# RF_Antenna_Power.net
KiCad netlist of a schematic drawn in Altium Designer
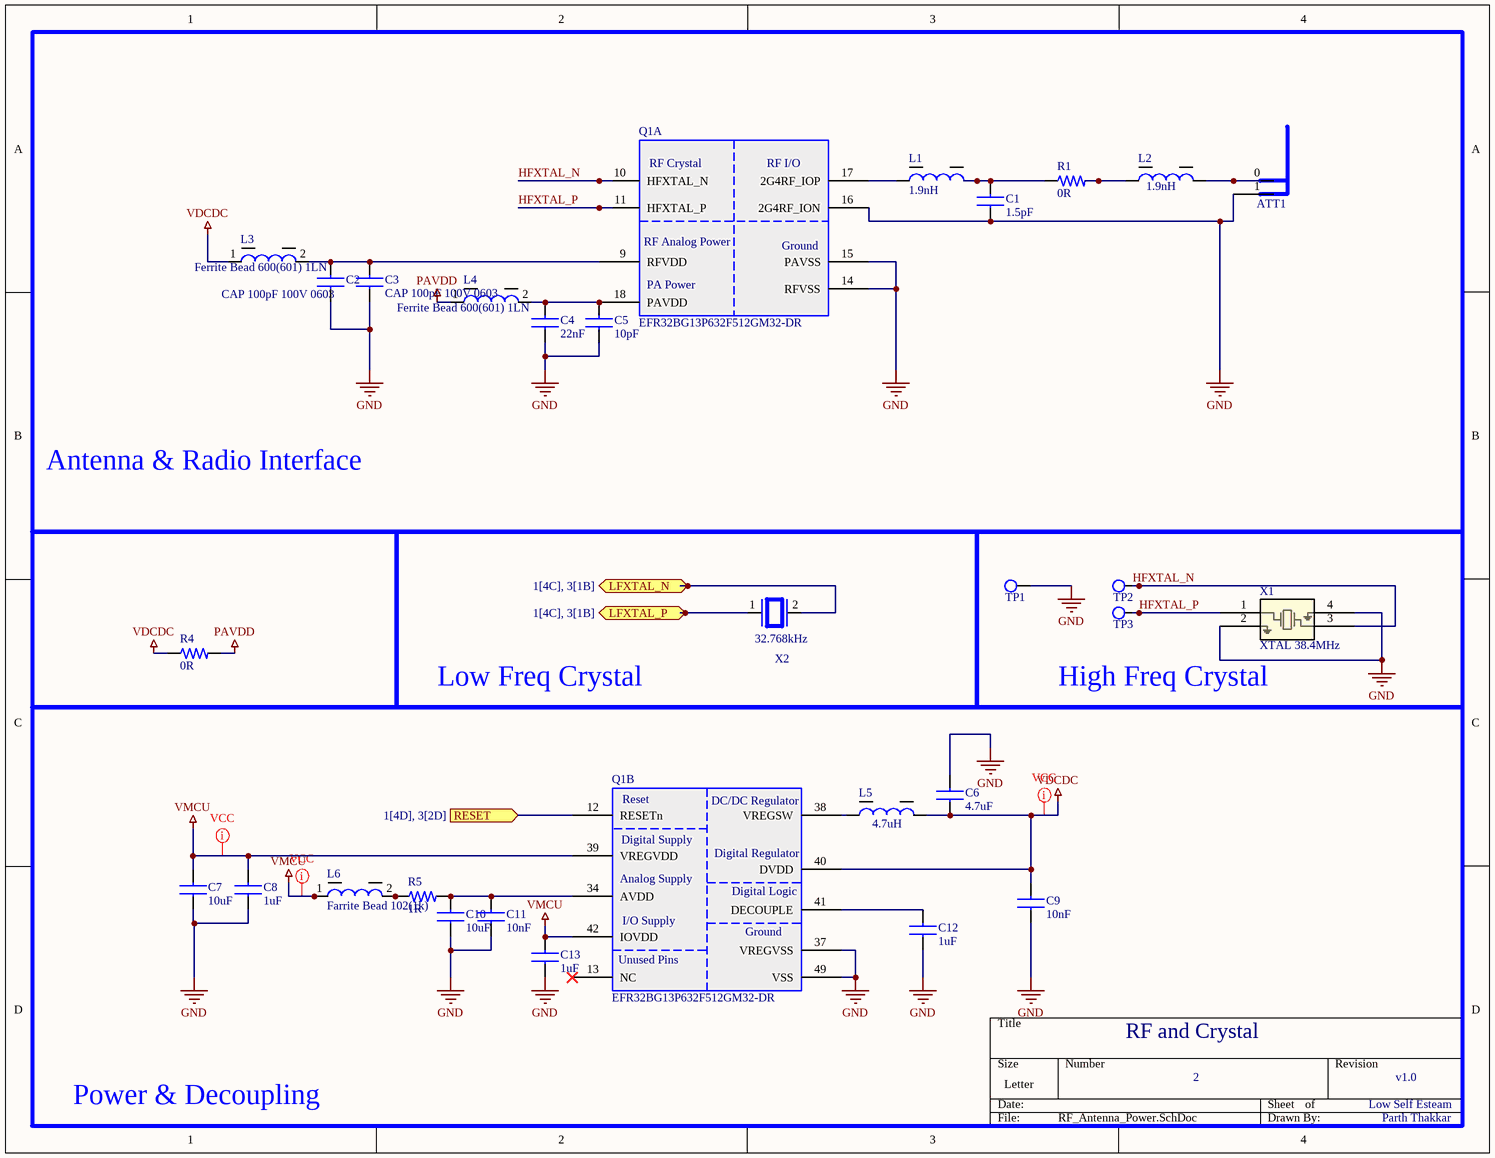
[diagram p0: RF_Antenna_Power.SchDoc]

(export (version "E")
  (design (tool "Eeschema 10.0.6"))
  (components
    (comp (ref "ATT1")
      (value "F_Interverted")
      (footprint "F_Inverted")
      (description "For 50Ohm impedence, Inverted F antenna")
      (libsource (lib "Keyboard_parts") (part "F_Interverted"))
    )
    (comp (ref "C1")
      (value "1.5pF")
      (footprint "Capacitor 0402")
      (fields
        (field (name "MANUFACTURER") "Murata")
        (field (name "MANUFACTURER PART NUMBER") "GJM1555C1H1R5WB01D")
        (field (name "Comment") "CAP 1.5pF 50V 0402")
      )
      (libsource (lib "Keyboard_parts") (part "CAP 1.5pF 50V 0402"))
    )
    (comp (ref "C2")
      (value "CAP 100pF 100V 0603")
      (footprint "Capacitor 0603")
      (fields
        (field (name "MANUFACTURER") "Murata")
        (field (name "MANUFACTURER PART NUMBER") "GCM1885C2A101JA16D")
      )
      (libsource (lib "Keyboard_parts") (part "CAP 100pF 100V 0603"))
    )
    (comp (ref "C3")
      (value "CAP 100pF 100V 0603")
      (footprint "Capacitor 0603")
      (fields
        (field (name "MANUFACTURER") "Murata")
        (field (name "MANUFACTURER PART NUMBER") "GCM1885C2A101JA16D")
      )
      (libsource (lib "Keyboard_parts") (part "CAP 100pF 100V 0603"))
    )
    (comp (ref "C4")
      (value "22nF")
      (footprint "Capacitor 0603")
      (fields
        (field (name "MANUFACTURER") "Murata")
        (field (name "MANUFACTURER PART NUMBER") "GRM155R71H223KA12D")
        (field (name "Comment") "CAP 220nF 50V 0603")
      )
      (libsource (lib "Keyboard_parts") (part "CAP 220nF 50V 0603"))
    )
    (comp (ref "C5")
      (value "10pF")
      (footprint "Capacitor 0603")
      (fields
        (field (name "MANUFACTURER") "Murata")
        (field (name "MANUFACTURER PART NUMBER") "GRM1555C1H100FA01D")
        (field (name "Comment") "CAP 10pF 50V 0603")
      )
      (libsource (lib "Keyboard_parts") (part "CAP 10pF 50V 0603"))
    )
    (comp (ref "C6")
      (value "4.7uF")
      (footprint "Capacitor 0603")
      (fields
        (field (name "MANUFACTURER") "Murata")
        (field (name "MANUFACTURER PART NUMBER") "GRT188R61E475KE13D")
        (field (name "Comment") "CAP 4.7uF 25V 0603")
      )
      (libsource (lib "Keyboard_parts") (part "CAP 4.7uF 25V 0603"))
    )
    (comp (ref "C7")
      (value "10uF")
      (footprint "Capacitor 0603")
      (fields
        (field (name "MANUFACTURER") "Murata")
        (field (name "MANUFACTURER PART NUMBER") "GRM188R61A106ME69D")
        (field (name "Comment") "CAP 10uF 10V 0603")
      )
      (libsource (lib "Keyboard_parts") (part "CAP 10uF 10V 0603"))
    )
    (comp (ref "C8")
      (value "1uF")
      (footprint "Capacitor 0603")
      (fields
        (field (name "MANUFACTURER") "Murata")
        (field (name "MANUFACTURER PART NUMBER") "GRM188R61A105KA61D")
        (field (name "Comment") "CAP 1uF 10V 0603")
      )
      (libsource (lib "Keyboard_parts") (part "CAP 1uF 10V 0603"))
    )
    (comp (ref "C9")
      (value "10nF")
      (footprint "Capacitor 0603")
      (fields
        (field (name "MANUFACTURER") "Murata")
        (field (name "MANUFACTURER PART NUMBER") "GCM188R72A103KA37D")
        (field (name "Comment") "CAP 0.1uF 100V 0603")
      )
      (libsource (lib "Keyboard_parts") (part "CAP 0.1uF 100V 0603"))
    )
    (comp (ref "C10")
      (value "10uF")
      (footprint "Capacitor 0603")
      (fields
        (field (name "MANUFACTURER") "Murata")
        (field (name "MANUFACTURER PART NUMBER") "GRM188R61A106ME69D")
        (field (name "Comment") "CAP 10uF 10V 0603")
      )
      (libsource (lib "Keyboard_parts") (part "CAP 10uF 10V 0603"))
    )
    (comp (ref "C11")
      (value "10nF")
      (footprint "Capacitor 0603")
      (fields
        (field (name "MANUFACTURER") "Murata")
        (field (name "MANUFACTURER PART NUMBER") "GCM188R72A103KA37D")
        (field (name "Comment") "CAP 10nF 100V 0603")
      )
      (libsource (lib "Keyboard_parts") (part "CAP 10nF 100V 0603"))
    )
    (comp (ref "C12")
      (value "1uF")
      (footprint "Capacitor 0603")
      (fields
        (field (name "MANUFACTURER") "Murata")
        (field (name "MANUFACTURER PART NUMBER") "GRM188R61A105KA61D")
        (field (name "Comment") "CAP 1uF 10V 0603")
      )
      (libsource (lib "Keyboard_parts") (part "CAP 1uF 10V 0603"))
    )
    (comp (ref "C13")
      (value "1uF")
      (footprint "Capacitor 0603")
      (fields
        (field (name "MANUFACTURER") "Murata")
        (field (name "MANUFACTURER PART NUMBER") "GRM188R61A105KA61D")
        (field (name "Comment") "CAP 1uF 10V 0603")
      )
      (libsource (lib "Keyboard_parts") (part "CAP 1uF 10V 0603"))
    )
    (comp (ref "L1")
      (value "1.9nH")
      (footprint "Ferrite 0402")
      (description "Inductor Chip 1.9nH 0.3nH Tolerance 2-Pin 0402 Paper T/R")
      (fields
        (field (name "MANUFACTURER") "Murata")
        (field (name "MANUFACTURER PART NUMBER") "LQG15WZ1N9S02D")
      )
      (libsource (lib "Keyboard_parts") (part "IND 1.9nH 0402"))
    )
    (comp (ref "L2")
      (value "1.9nH")
      (footprint "Ferrite 0402")
      (description "Inductor Chip 1.9nH 0.3nH Tolerance 2-Pin 0402 Paper T/R")
      (fields
        (field (name "MANUFACTURER") "Murata")
        (field (name "MANUFACTURER PART NUMBER") "LQG15WZ1N9S02D")
      )
      (libsource (lib "Keyboard_parts") (part "IND 1.9nH 0402"))
    )
    (comp (ref "L3")
      (value "Ferrite Bead 600(601) 1LN")
      (footprint "Ferrite 0603")
      (description "RFVDD, PAVDD, EFR")
      (fields
        (field (name "MANUFACTURER") "Murata")
        (field (name "MANUFACTURER PART NUMBER") "BLM18AG601SN1D")
      )
      (libsource (lib "Keyboard_parts") (part "Ferrite Bead 600(601) 1LN"))
    )
    (comp (ref "L4")
      (value "Ferrite Bead 600(601) 1LN")
      (footprint "Ferrite 0603")
      (description "RFVDD, PAVDD, EFR")
      (fields
        (field (name "MANUFACTURER") "Murata")
        (field (name "MANUFACTURER PART NUMBER") "BLM18AG601SN1D")
      )
      (libsource (lib "Keyboard_parts") (part "Ferrite Bead 600(601) 1LN"))
    )
    (comp (ref "L5")
      (value "IND 4.7uH 1515")
      (footprint "IND 22uH (1.6x4.3)")
      (description "General Purpose Inductor, 4.7uH, 30%, 1 Element, Ferrite-Core, SMD, 1515")
      (fields
        (field (name "MANUFACTURER") "Wurth Electronics")
        (field (name "MANUFACTURER PART NUMBER") "744031004")
        (field (name "INDUCTANCE-NOM (L)") "4.7uH")
      )
      (libsource (lib "Keyboard_parts") (part "IND 4.7uH 1515"))
    )
    (comp (ref "L6")
      (value "Farrite Bead 102(1k)")
      (footprint "Ferrite 0402")
      (description "Ferrite Chip, 1 Function(s), 0.05A, 2 Pin(s)")
      (fields
        (field (name "MANUFACTURER") "Wurth Electronics")
        (field (name "MANUFACTURER PART NUMBER") "742841210")
      )
      (libsource (lib "Keyboard_parts") (part "Farrite Bead 102(1k)"))
    )
    (comp (ref "Q1")
      (value "EFR32BG13P632F512GM32-DR")
      (footprint "EFR32BG")
      (description "BLue Gecko")
      (fields (field (name "MANUFACTURER") "Silicon Labs"))
      (libsource (lib "Keyboard_parts") (part "EFR32BG13P632F512GM32-DR"))
    )
    (comp (ref "R1")
      (value "0R")
      (footprint "Resistor 0402")
      (description "Metal Glaze/thick Film, 0.0625W, 0ohm, Surface Mount, 0402")
      (fields
        (field (name "MANUFACTURER") "Yageo")
        (field (name "MANUFACTURER PART NUMBER") "RC0402JR-070RL")
      )
      (libsource (lib "Keyboard_parts") (part "RES 0R 0402"))
    )
    (comp (ref "R4")
      (value "0R")
      (footprint "Resistor 0402")
      (description "Metal Glaze/thick Film, 0.0625W, 0ohm, Surface Mount, 0402")
      (fields
        (field (name "MANUFACTURER") "Yageo")
        (field (name "MANUFACTURER PART NUMBER") "RC0402JR-070RL")
      )
      (libsource (lib "Keyboard_parts") (part "RES 0R 0402"))
    )
    (comp (ref "R5")
      (value "1R")
      (footprint "Resistor 0603")
      (fields
        (field (name "MANUFACTURER") "Yageo")
        (field (name "MANUFACTURER PART NUMBER") "RC0603FR-071RL")
        (field (name "TOLERANCE") "1%")
      )
      (libsource (lib "Keyboard_parts") (part "RES 1R 0603"))
    )
    (comp (ref "TP1")
      (value "Test point")
      (footprint "Test Point")
      (libsource (lib "Keyboard_parts") (part "Test point"))
    )
    (comp (ref "TP2")
      (value "Test point")
      (footprint "Test Point")
      (libsource (lib "Keyboard_parts") (part "Test point"))
    )
    (comp (ref "TP3")
      (value "Test point")
      (footprint "Test Point")
      (libsource (lib "Keyboard_parts") (part "Test point"))
    )
    (comp (ref "X1")
      (value "XTAL 38.4MHz")
      (footprint "XTAL 38.4MHz")
      (description "Crystal 38.4000MHZ 10PF SMD")
      (fields
        (field (name "MANUFACTURER") "Murata")
        (field (name "MANUFACTURER PART NUMBER") "XRCGB38M400F1S3JR0")
      )
      (libsource (lib "Keyboard_parts") (part "XTAL 38.4MHz"))
    )
    (comp (ref "X2")
      (value "32.768kHz")
      (footprint "XTAL_32.768KHZ-T")
      (description "Parallel - Fundamental Quartz Crystal, 0.032768MHz Nom")
      (fields
        (field (name "MANUFACTURER") "Abracon")
        (field (name "MANUFACTURER PART NUMBER") "ABS07-32.768KHZ-T")
      )
      (libsource (lib "Keyboard_parts") (part "XTAL 32.768kHz"))
    )
  )
  (nets
    (net (code "1") (name "/HFXTAL_N") (class "Default")
      (node (ref "Q1") (pin "10") (pinfunction "HFXTAL_N_10") (pintype "passive"))
      (node (ref "TP2") (pin "1") (pinfunction "1_1") (pintype "passive"))
      (node (ref "X1") (pin "3") (pinfunction "3_3") (pintype "passive"))
    )
    (net (code "2") (name "/HFXTAL_P") (class "Default")
      (node (ref "Q1") (pin "11") (pinfunction "HFXTAL_P_11") (pintype "passive"))
      (node (ref "TP3") (pin "1") (pinfunction "1_1") (pintype "passive"))
      (node (ref "X1") (pin "1") (pinfunction "1_1") (pintype "passive"))
    )
    (net (code "3") (name "/LFXTAL_N") (class "Default")
      (node (ref "X2") (pin "2") (pinfunction "2_2") (pintype "passive"))
    )
    (net (code "4") (name "/LFXTAL_P") (class "Default")
      (node (ref "X2") (pin "1") (pinfunction "1_1") (pintype "passive"))
    )
    (net (code "5") (name "/RESET") (class "Default")
      (node (ref "Q1") (pin "12") (pinfunction "RESETn_12") (pintype "passive"))
    )
    (net (code "6") (name "GND") (class "Default")
      (node (ref "ATT1") (pin "1") (pinfunction "GND_1") (pintype "passive"))
      (node (ref "C1") (pin "2") (pinfunction "2_2") (pintype "passive"))
      (node (ref "C10") (pin "2") (pinfunction "2_2") (pintype "passive"))
      (node (ref "C11") (pin "2") (pinfunction "2_2") (pintype "passive"))
      (node (ref "C12") (pin "2") (pinfunction "2_2") (pintype "passive"))
      (node (ref "C13") (pin "2") (pinfunction "2_2") (pintype "passive"))
      (node (ref "C2") (pin "2") (pinfunction "2_2") (pintype "passive"))
      (node (ref "C3") (pin "2") (pinfunction "2_2") (pintype "passive"))
      (node (ref "C4") (pin "2") (pinfunction "2_2") (pintype "passive"))
      (node (ref "C5") (pin "2") (pinfunction "2_2") (pintype "passive"))
      (node (ref "C6") (pin "2") (pinfunction "2_2") (pintype "passive"))
      (node (ref "C7") (pin "2") (pinfunction "2_2") (pintype "passive"))
      (node (ref "C8") (pin "2") (pinfunction "2_2") (pintype "passive"))
      (node (ref "C9") (pin "2") (pinfunction "2_2") (pintype "passive"))
      (node (ref "Q1") (pin "14") (pinfunction "RFVSS_14") (pintype "power_in"))
      (node (ref "Q1") (pin "15") (pinfunction "PAVSS_15") (pintype "power_in"))
      (node (ref "Q1") (pin "16") (pinfunction "2G4RF_ION_16") (pintype "passive"))
      (node (ref "Q1") (pin "37") (pinfunction "VREGVSS_37") (pintype "power_in"))
      (node (ref "Q1") (pin "49") (pinfunction "VSS_49") (pintype "power_in"))
      (node (ref "TP1") (pin "1") (pinfunction "1_1") (pintype "passive"))
      (node (ref "X1") (pin "2") (pinfunction "2_2") (pintype "passive"))
      (node (ref "X1") (pin "4") (pinfunction "4_4") (pintype "passive"))
    )
    (net (code "7") (name "Net-(ATT1-FEED)") (class "Default")
      (node (ref "ATT1") (pin "0") (pinfunction "FEED_0") (pintype "passive"))
      (node (ref "L2") (pin "2") (pinfunction "2_2") (pintype "passive"))
    )
    (net (code "8") (name "Net-(C1-Pad1)") (class "Default")
      (node (ref "C1") (pin "1") (pinfunction "1_1") (pintype "passive"))
      (node (ref "L1") (pin "2") (pinfunction "2_2") (pintype "passive"))
      (node (ref "R1") (pin "1") (pinfunction "1_1") (pintype "passive"))
    )
    (net (code "9") (name "Net-(L2-Pad1)") (class "Default")
      (node (ref "L2") (pin "1") (pinfunction "1_1") (pintype "passive"))
      (node (ref "R1") (pin "2") (pinfunction "2_2") (pintype "passive"))
    )
    (net (code "10") (name "Net-(L6-Pad2)") (class "Default")
      (node (ref "L6") (pin "2") (pinfunction "2_2") (pintype "passive"))
      (node (ref "R5") (pin "1") (pinfunction "1_1") (pintype "passive"))
    )
    (net (code "11") (name "Net-(Q1A-2G4RF_IOP)") (class "Default")
      (node (ref "L1") (pin "1") (pinfunction "1_1") (pintype "passive"))
      (node (ref "Q1") (pin "17") (pinfunction "2G4RF_IOP_17") (pintype "passive"))
    )
    (net (code "12") (name "Net-(Q1A-PAVDD)") (class "Default")
      (node (ref "C4") (pin "1") (pinfunction "1_1") (pintype "passive"))
      (node (ref "C5") (pin "1") (pinfunction "1_1") (pintype "passive"))
      (node (ref "L4") (pin "2") (pinfunction "2_2") (pintype "passive"))
      (node (ref "Q1") (pin "18") (pinfunction "PAVDD_18") (pintype "power_in"))
    )
    (net (code "13") (name "Net-(Q1A-RFVDD)") (class "Default")
      (node (ref "C2") (pin "1") (pinfunction "1_1") (pintype "passive"))
      (node (ref "C3") (pin "1") (pinfunction "1_1") (pintype "passive"))
      (node (ref "L3") (pin "2") (pinfunction "2_2") (pintype "passive"))
      (node (ref "Q1") (pin "9") (pinfunction "RFVDD_9") (pintype "power_in"))
    )
    (net (code "14") (name "Net-(Q1B-AVDD)") (class "Default")
      (node (ref "C10") (pin "1") (pinfunction "1_1") (pintype "passive"))
      (node (ref "C11") (pin "1") (pinfunction "1_1") (pintype "passive"))
      (node (ref "Q1") (pin "34") (pinfunction "AVDD_34") (pintype "power_in"))
      (node (ref "R5") (pin "2") (pinfunction "2_2") (pintype "passive"))
    )
    (net (code "15") (name "Net-(Q1B-DECOUPLE)") (class "Default")
      (node (ref "C12") (pin "1") (pinfunction "1_1") (pintype "passive"))
      (node (ref "Q1") (pin "41") (pinfunction "DECOUPLE_41") (pintype "passive"))
    )
    (net (code "16") (name "Net-(Q1B-VREGSW)") (class "Default")
      (node (ref "L5") (pin "1") (pinfunction "1_1") (pintype "passive"))
      (node (ref "Q1") (pin "38") (pinfunction "VREGSW_38") (pintype "power_in"))
    )
    (net (code "17") (name "PAVDD") (class "Default")
      (node (ref "L4") (pin "1") (pinfunction "1_1") (pintype "passive"))
      (node (ref "R4") (pin "2") (pinfunction "2_2") (pintype "passive"))
    )
    (net (code "18") (name "VDCDC") (class "Default")
      (node (ref "C6") (pin "1") (pinfunction "1_1") (pintype "passive"))
      (node (ref "C9") (pin "1") (pinfunction "1_1") (pintype "passive"))
      (node (ref "L3") (pin "1") (pinfunction "1_1") (pintype "passive"))
      (node (ref "L5") (pin "2") (pinfunction "2_2") (pintype "passive"))
      (node (ref "Q1") (pin "40") (pinfunction "DVDD_40") (pintype "power_in"))
      (node (ref "R4") (pin "1") (pinfunction "1_1") (pintype "passive"))
    )
    (net (code "19") (name "VMCU") (class "Default")
      (node (ref "C13") (pin "1") (pinfunction "1_1") (pintype "passive"))
      (node (ref "C7") (pin "1") (pinfunction "1_1") (pintype "passive"))
      (node (ref "C8") (pin "1") (pinfunction "1_1") (pintype "passive"))
      (node (ref "L6") (pin "1") (pinfunction "1_1") (pintype "passive"))
      (node (ref "Q1") (pin "39") (pinfunction "VREGVDD_39") (pintype "power_in"))
      (node (ref "Q1") (pin "42") (pinfunction "IOVDD_42") (pintype "power_in"))
    )
    (net (code "20") (name "unconnected-(Q1B-NC-Pad13)") (class "Default")
      (node (ref "Q1") (pin "13") (pinfunction "NC_13") (pintype "passive+no_connect"))
    )
  )
)
